# PX4FMUv2_4_6_02.net
KiCad netlist of a schematic drawn in Altium Designer
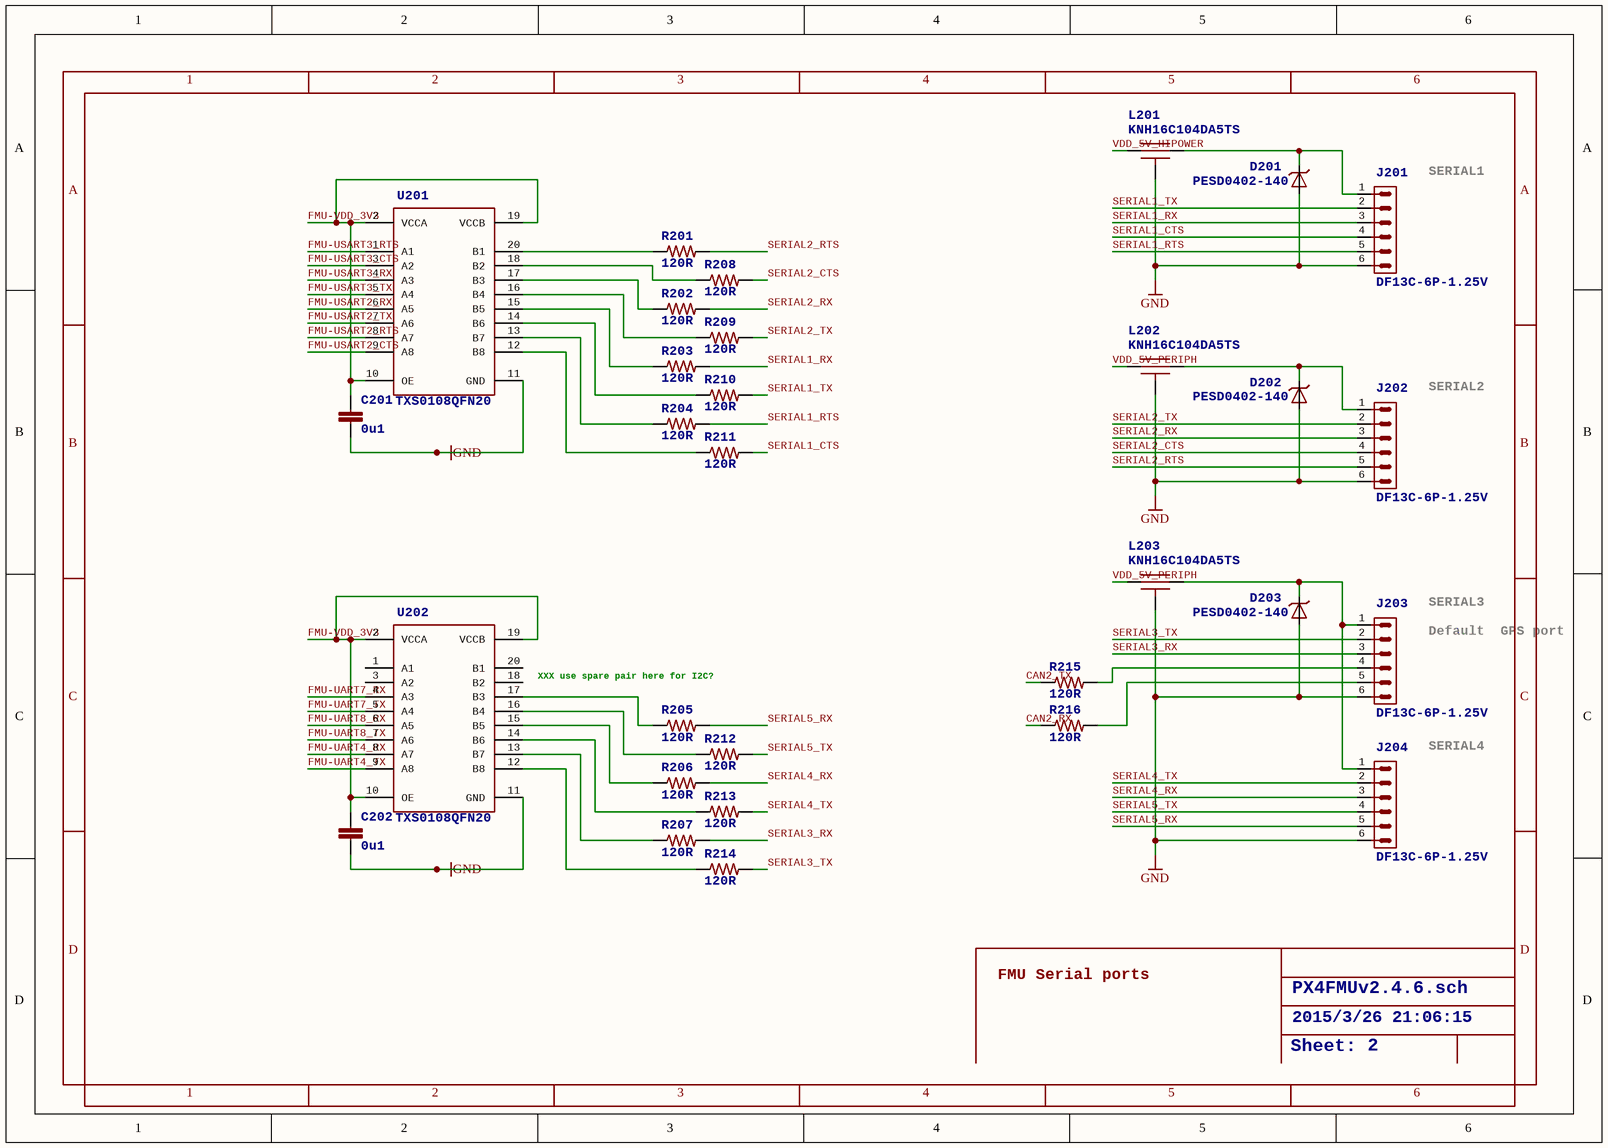
[diagram p0: PX4FMUv2.4.6_02.SchDoc]

(export (version "E")
  (design (tool "Eeschema 10.0.6"))
  (components
    (comp (ref "C201")
      (value "0u1")
      (footprint "0402-CAP")
      (description "<b>Capacitor</b>\nStandard 0603 ceramic capacitor, and 0.1\" leaded capacitor.")
      (fields (field (name "PARTNO") "CC0402ZRY5V7BB104"))
      (libsource (lib "pixhawk2") (part "CAP0402"))
    )
    (comp (ref "C202")
      (value "0u1")
      (footprint "0402-CAP")
      (description "<b>Capacitor</b>\nStandard 0603 ceramic capacitor, and 0.1\" leaded capacitor.")
      (fields (field (name "PARTNO") "CC0402ZRY5V7BB104"))
      (libsource (lib "pixhawk2") (part "CAP0402"))
    )
    (comp (ref "D201")
      (value "PESD0402-140")
      (footprint "0402-TVS")
      (libsource (lib "pixhawk2") (part "DIODE-TVS"))
    )
    (comp (ref "D202")
      (value "PESD0402-140")
      (footprint "0402-TVS")
      (libsource (lib "pixhawk2") (part "DIODE-TVS"))
    )
    (comp (ref "D203")
      (value "PESD0402-140")
      (footprint "0402-TVS")
      (libsource (lib "pixhawk2") (part "DIODE-TVS"))
    )
    (comp (ref "J201")
      (value "DF13C-6P-1.25V")
      (footprint "DF13C-6P-1.25V")
      (description "DF13-6P\n1.25mm Pitch Miniature Crimping Connector.")
      (fields (field (name "PARTNO") "DF13C-6P-1.25V(20)"))
      (libsource (lib "con-hirose-df13") (part "DF13-6P-1.25V"))
    )
    (comp (ref "J202")
      (value "DF13C-6P-1.25V")
      (footprint "DF13C-6P-1.25V")
      (description "DF13-6P\n1.25mm Pitch Miniature Crimping Connector.")
      (fields (field (name "PARTNO") "DF13C-6P-1.25V(20)"))
      (libsource (lib "con-hirose-df13") (part "DF13-6P-1.25V"))
    )
    (comp (ref "J203")
      (value "DF13C-6P-1.25V")
      (footprint "DF13C-6P-1.25V")
      (description "DF13-6P\n1.25mm Pitch Miniature Crimping Connector.")
      (fields (field (name "PARTNO") "DF13C-6P-1.25V(20)"))
      (libsource (lib "con-hirose-df13") (part "DF13-6P-1.25V"))
    )
    (comp (ref "J204")
      (value "DF13C-6P-1.25V")
      (footprint "DF13C-6P-1.25V")
      (description "DF13-6P\n1.25mm Pitch Miniature Crimping Connector.")
      (fields (field (name "PARTNO") "DF13C-6P-1.25V(20)"))
      (libsource (lib "con-hirose-df13") (part "DF13-6P-1.25V"))
    )
    (comp (ref "L201")
      (value "KNH16C104DA5TS")
      (footprint "KYOCERA-KNH16-DA")
      (description "Kyocera KNH16C104DA5TS EMI filter")
      (libsource (lib "pixhawk2") (part "KNH16C104DA5TS"))
    )
    (comp (ref "L202")
      (value "KNH16C104DA5TS")
      (footprint "KYOCERA-KNH16-DA")
      (description "Kyocera KNH16C104DA5TS EMI filter")
      (libsource (lib "pixhawk2") (part "KNH16C104DA5TS"))
    )
    (comp (ref "L203")
      (value "KNH16C104DA5TS")
      (footprint "KYOCERA-KNH16-DA")
      (description "Kyocera KNH16C104DA5TS EMI filter")
      (libsource (lib "pixhawk2") (part "KNH16C104DA5TS"))
    )
    (comp (ref "R201")
      (value "120R")
      (footprint "0402-RES")
      (fields (field (name "PARTNO") "RC0402FR-07120RL"))
      (libsource (lib "pixhawk2") (part "RESISTOR0402-RES"))
    )
    (comp (ref "R202")
      (value "120R")
      (footprint "0402-RES")
      (fields (field (name "PARTNO") "RC0402FR-07120RL"))
      (libsource (lib "pixhawk2") (part "RESISTOR0402-RES"))
    )
    (comp (ref "R203")
      (value "120R")
      (footprint "0402-RES")
      (fields (field (name "PARTNO") "RC0402FR-07120RL"))
      (libsource (lib "pixhawk2") (part "RESISTOR0402-RES"))
    )
    (comp (ref "R204")
      (value "120R")
      (footprint "0402-RES")
      (fields (field (name "PARTNO") "RC0402FR-07120RL"))
      (libsource (lib "pixhawk2") (part "RESISTOR0402-RES"))
    )
    (comp (ref "R205")
      (value "120R")
      (footprint "0402-RES")
      (fields (field (name "PARTNO") "RC0402FR-07120RL"))
      (libsource (lib "pixhawk2") (part "RESISTOR0402-RES"))
    )
    (comp (ref "R206")
      (value "120R")
      (footprint "0402-RES")
      (fields (field (name "PARTNO") "RC0402FR-07120RL"))
      (libsource (lib "pixhawk2") (part "RESISTOR0402-RES"))
    )
    (comp (ref "R207")
      (value "120R")
      (footprint "0402-RES")
      (fields (field (name "PARTNO") "RC0402FR-07120RL"))
      (libsource (lib "pixhawk2") (part "RESISTOR0402-RES"))
    )
    (comp (ref "R208")
      (value "120R")
      (footprint "0402-RES")
      (fields (field (name "PARTNO") "RC0402FR-07120RL"))
      (libsource (lib "pixhawk2") (part "RESISTOR0402-RES"))
    )
    (comp (ref "R209")
      (value "120R")
      (footprint "0402-RES")
      (fields (field (name "PARTNO") "RC0402FR-07120RL"))
      (libsource (lib "pixhawk2") (part "RESISTOR0402-RES"))
    )
    (comp (ref "R210")
      (value "120R")
      (footprint "0402-RES")
      (fields (field (name "PARTNO") "RC0402FR-07120RL"))
      (libsource (lib "pixhawk2") (part "RESISTOR0402-RES"))
    )
    (comp (ref "R211")
      (value "120R")
      (footprint "0402-RES")
      (fields (field (name "PARTNO") "RC0402FR-07120RL"))
      (libsource (lib "pixhawk2") (part "RESISTOR0402-RES"))
    )
    (comp (ref "R212")
      (value "120R")
      (footprint "0402-RES")
      (fields (field (name "PARTNO") "RC0402FR-07120RL"))
      (libsource (lib "pixhawk2") (part "RESISTOR0402-RES"))
    )
    (comp (ref "R213")
      (value "120R")
      (footprint "0402-RES")
      (fields (field (name "PARTNO") "RC0402FR-07120RL"))
      (libsource (lib "pixhawk2") (part "RESISTOR0402-RES"))
    )
    (comp (ref "R214")
      (value "120R")
      (footprint "0402-RES")
      (fields (field (name "PARTNO") "RC0402FR-07120RL"))
      (libsource (lib "pixhawk2") (part "RESISTOR0402-RES"))
    )
    (comp (ref "R215")
      (value "120R")
      (footprint "0402-RES")
      (fields (field (name "PARTNO") "RC0402FR-07120RL"))
      (libsource (lib "pixhawk2") (part "RESISTOR0402-RES"))
    )
    (comp (ref "R216")
      (value "120R")
      (footprint "0402-RES")
      (fields (field (name "PARTNO") "RC0402FR-07120RL"))
      (libsource (lib "pixhawk2") (part "RESISTOR0402-RES"))
    )
    (comp (ref "U201")
      (value "TXS0108QFN20")
      (footprint "QFN20-RGY")
      (fields (field (name "PARTNO") "TXS0108ERGYR"))
      (libsource (lib "pixhawk2") (part "TXS0108QFN20"))
    )
    (comp (ref "U202")
      (value "TXS0108QFN20")
      (footprint "QFN20-RGY")
      (fields (field (name "PARTNO") "TXS0108ERGYR"))
      (libsource (lib "pixhawk2") (part "TXS0108QFN20"))
    )
  )
  (nets
    (net (code "1") (name "/CAN2_RX") (class "Default")
      (node (ref "R216") (pin "P$1") (pinfunction "1_P$1") (pintype "passive"))
    )
    (net (code "2") (name "/CAN2_TX") (class "Default")
      (node (ref "R215") (pin "P$1") (pinfunction "1_P$1") (pintype "passive"))
    )
    (net (code "3") (name "/FMU-UART4_RX") (class "Default")
      (node (ref "U202") (pin "8") (pinfunction "A7_8") (pintype "passive"))
    )
    (net (code "4") (name "/FMU-UART4_TX") (class "Default")
      (node (ref "U202") (pin "9") (pinfunction "A8_9") (pintype "passive"))
    )
    (net (code "5") (name "/FMU-UART7_RX") (class "Default")
      (node (ref "U202") (pin "4") (pinfunction "A3_4") (pintype "passive"))
    )
    (net (code "6") (name "/FMU-UART7_TX") (class "Default")
      (node (ref "U202") (pin "5") (pinfunction "A4_5") (pintype "passive"))
    )
    (net (code "7") (name "/FMU-UART8_RX") (class "Default")
      (node (ref "U202") (pin "6") (pinfunction "A5_6") (pintype "passive"))
    )
    (net (code "8") (name "/FMU-UART8_TX") (class "Default")
      (node (ref "U202") (pin "7") (pinfunction "A6_7") (pintype "passive"))
    )
    (net (code "9") (name "/FMU-USART2_CTS") (class "Default")
      (node (ref "U201") (pin "9") (pinfunction "A8_9") (pintype "passive"))
    )
    (net (code "10") (name "/FMU-USART2_RTS") (class "Default")
      (node (ref "U201") (pin "8") (pinfunction "A7_8") (pintype "passive"))
    )
    (net (code "11") (name "/FMU-USART2_RX") (class "Default")
      (node (ref "U201") (pin "6") (pinfunction "A5_6") (pintype "passive"))
    )
    (net (code "12") (name "/FMU-USART2_TX") (class "Default")
      (node (ref "U201") (pin "7") (pinfunction "A6_7") (pintype "passive"))
    )
    (net (code "13") (name "/FMU-USART3_CTS") (class "Default")
      (node (ref "U201") (pin "3") (pinfunction "A2_3") (pintype "passive"))
    )
    (net (code "14") (name "/FMU-USART3_RTS") (class "Default")
      (node (ref "U201") (pin "1") (pinfunction "A1_1") (pintype "passive"))
    )
    (net (code "15") (name "/FMU-USART3_RX") (class "Default")
      (node (ref "U201") (pin "4") (pinfunction "A3_4") (pintype "passive"))
    )
    (net (code "16") (name "/FMU-USART3_TX") (class "Default")
      (node (ref "U201") (pin "5") (pinfunction "A4_5") (pintype "passive"))
    )
    (net (code "17") (name "/FMU-VDD_3V3") (class "Default")
      (node (ref "C201") (pin "P$1") (pinfunction "1_P$1") (pintype "passive"))
      (node (ref "C202") (pin "P$1") (pinfunction "1_P$1") (pintype "passive"))
      (node (ref "U201") (pin "10") (pinfunction "OE_10") (pintype "passive"))
      (node (ref "U201") (pin "19") (pinfunction "VCCB_19") (pintype "passive"))
      (node (ref "U201") (pin "2") (pinfunction "VCCA_2") (pintype "passive"))
      (node (ref "U202") (pin "10") (pinfunction "OE_10") (pintype "passive"))
      (node (ref "U202") (pin "19") (pinfunction "VCCB_19") (pintype "passive"))
      (node (ref "U202") (pin "2") (pinfunction "VCCA_2") (pintype "passive"))
    )
    (net (code "18") (name "/SERIAL1_CTS") (class "Default")
      (node (ref "J201") (pin "4") (pinfunction "4_4") (pintype "passive"))
      (node (ref "R211") (pin "P$2") (pinfunction "2_P$2") (pintype "passive"))
    )
    (net (code "19") (name "/SERIAL1_RTS") (class "Default")
      (node (ref "J201") (pin "5") (pinfunction "5_5") (pintype "passive"))
      (node (ref "R204") (pin "P$2") (pinfunction "2_P$2") (pintype "passive"))
    )
    (net (code "20") (name "/SERIAL1_RX") (class "Default")
      (node (ref "J201") (pin "3") (pinfunction "3_3") (pintype "passive"))
      (node (ref "R203") (pin "P$2") (pinfunction "2_P$2") (pintype "passive"))
    )
    (net (code "21") (name "/SERIAL1_TX") (class "Default")
      (node (ref "J201") (pin "2") (pinfunction "2_2") (pintype "passive"))
      (node (ref "R210") (pin "P$2") (pinfunction "2_P$2") (pintype "passive"))
    )
    (net (code "22") (name "/SERIAL2_CTS") (class "Default")
      (node (ref "J202") (pin "4") (pinfunction "4_4") (pintype "passive"))
      (node (ref "R208") (pin "P$2") (pinfunction "2_P$2") (pintype "passive"))
    )
    (net (code "23") (name "/SERIAL2_RTS") (class "Default")
      (node (ref "J202") (pin "5") (pinfunction "5_5") (pintype "passive"))
      (node (ref "R201") (pin "P$2") (pinfunction "2_P$2") (pintype "passive"))
    )
    (net (code "24") (name "/SERIAL2_RX") (class "Default")
      (node (ref "J202") (pin "3") (pinfunction "3_3") (pintype "passive"))
      (node (ref "R202") (pin "P$2") (pinfunction "2_P$2") (pintype "passive"))
    )
    (net (code "25") (name "/SERIAL2_TX") (class "Default")
      (node (ref "J202") (pin "2") (pinfunction "2_2") (pintype "passive"))
      (node (ref "R209") (pin "P$2") (pinfunction "2_P$2") (pintype "passive"))
    )
    (net (code "26") (name "/SERIAL3_RX") (class "Default")
      (node (ref "J203") (pin "3") (pinfunction "3_3") (pintype "passive"))
      (node (ref "R207") (pin "P$2") (pinfunction "2_P$2") (pintype "passive"))
    )
    (net (code "27") (name "/SERIAL3_TX") (class "Default")
      (node (ref "J203") (pin "2") (pinfunction "2_2") (pintype "passive"))
      (node (ref "R214") (pin "P$2") (pinfunction "2_P$2") (pintype "passive"))
    )
    (net (code "28") (name "/SERIAL4_RX") (class "Default")
      (node (ref "J204") (pin "3") (pinfunction "3_3") (pintype "passive"))
      (node (ref "R206") (pin "P$2") (pinfunction "2_P$2") (pintype "passive"))
    )
    (net (code "29") (name "/SERIAL4_TX") (class "Default")
      (node (ref "J204") (pin "2") (pinfunction "2_2") (pintype "passive"))
      (node (ref "R213") (pin "P$2") (pinfunction "2_P$2") (pintype "passive"))
    )
    (net (code "30") (name "/SERIAL5_RX") (class "Default")
      (node (ref "J204") (pin "5") (pinfunction "5_5") (pintype "passive"))
      (node (ref "R205") (pin "P$2") (pinfunction "2_P$2") (pintype "passive"))
    )
    (net (code "31") (name "/SERIAL5_TX") (class "Default")
      (node (ref "J204") (pin "4") (pinfunction "4_4") (pintype "passive"))
      (node (ref "R212") (pin "P$2") (pinfunction "2_P$2") (pintype "passive"))
    )
    (net (code "32") (name "/VDD_5V_HIPOWER") (class "Default")
      (node (ref "L201") (pin "P$1") (pinfunction "P$1_P$1") (pintype "passive"))
    )
    (net (code "33") (name "/VDD_5V_PERIPH") (class "Default")
      (node (ref "L202") (pin "P$1") (pinfunction "P$1_P$1") (pintype "passive"))
      (node (ref "L203") (pin "P$1") (pinfunction "P$1_P$1") (pintype "passive"))
    )
    (net (code "34") (name "GND") (class "Default")
      (node (ref "C201") (pin "P$2") (pinfunction "2_P$2") (pintype "passive"))
      (node (ref "C202") (pin "P$2") (pinfunction "2_P$2") (pintype "passive"))
      (node (ref "D201") (pin "A") (pinfunction "A_A") (pintype "passive"))
      (node (ref "D202") (pin "A") (pinfunction "A_A") (pintype "passive"))
      (node (ref "D203") (pin "A") (pinfunction "A_A") (pintype "passive"))
      (node (ref "J201") (pin "6") (pinfunction "6_6") (pintype "passive"))
      (node (ref "J202") (pin "6") (pinfunction "6_6") (pintype "passive"))
      (node (ref "J203") (pin "6") (pinfunction "6_6") (pintype "passive"))
      (node (ref "J204") (pin "6") (pinfunction "6_6") (pintype "passive"))
      (node (ref "L201") (pin "P$3_P$4_P$5") (pinfunction "P$3_P$3_P$4_P$5") (pintype "passive"))
      (node (ref "L202") (pin "P$3_P$4_P$5") (pinfunction "P$3_P$3_P$4_P$5") (pintype "passive"))
      (node (ref "L203") (pin "P$3_P$4_P$5") (pinfunction "P$3_P$3_P$4_P$5") (pintype "passive"))
      (node (ref "U201") (pin "11") (pinfunction "GND_11") (pintype "open_emitter"))
      (node (ref "U202") (pin "11") (pinfunction "GND_11") (pintype "open_emitter"))
    )
    (net (code "35") (name "Net-(D201-PadC)") (class "Default")
      (node (ref "D201") (pin "C") (pinfunction "C_C") (pintype "passive"))
      (node (ref "J201") (pin "1") (pinfunction "1_1") (pintype "passive"))
      (node (ref "L201") (pin "P$2") (pinfunction "P$2_P$2") (pintype "passive"))
    )
    (net (code "36") (name "Net-(D202-PadC)") (class "Default")
      (node (ref "D202") (pin "C") (pinfunction "C_C") (pintype "passive"))
      (node (ref "J202") (pin "1") (pinfunction "1_1") (pintype "passive"))
      (node (ref "L202") (pin "P$2") (pinfunction "P$2_P$2") (pintype "passive"))
    )
    (net (code "37") (name "Net-(D203-PadC)") (class "Default")
      (node (ref "D203") (pin "C") (pinfunction "C_C") (pintype "passive"))
      (node (ref "J203") (pin "1") (pinfunction "1_1") (pintype "passive"))
      (node (ref "J204") (pin "1") (pinfunction "1_1") (pintype "passive"))
      (node (ref "L203") (pin "P$2") (pinfunction "P$2_P$2") (pintype "passive"))
    )
    (net (code "38") (name "Net-(R201-1)") (class "Default")
      (node (ref "R201") (pin "P$1") (pinfunction "1_P$1") (pintype "passive"))
      (node (ref "U201") (pin "20") (pinfunction "B1_20") (pintype "passive"))
    )
    (net (code "39") (name "Net-(R202-1)") (class "Default")
      (node (ref "R202") (pin "P$1") (pinfunction "1_P$1") (pintype "passive"))
      (node (ref "U201") (pin "17") (pinfunction "B3_17") (pintype "passive"))
    )
    (net (code "40") (name "Net-(R203-1)") (class "Default")
      (node (ref "R203") (pin "P$1") (pinfunction "1_P$1") (pintype "passive"))
      (node (ref "U201") (pin "15") (pinfunction "B5_15") (pintype "passive"))
    )
    (net (code "41") (name "Net-(R204-1)") (class "Default")
      (node (ref "R204") (pin "P$1") (pinfunction "1_P$1") (pintype "passive"))
      (node (ref "U201") (pin "13") (pinfunction "B7_13") (pintype "passive"))
    )
    (net (code "42") (name "Net-(R205-1)") (class "Default")
      (node (ref "R205") (pin "P$1") (pinfunction "1_P$1") (pintype "passive"))
      (node (ref "U202") (pin "17") (pinfunction "B3_17") (pintype "passive"))
    )
    (net (code "43") (name "Net-(R206-1)") (class "Default")
      (node (ref "R206") (pin "P$1") (pinfunction "1_P$1") (pintype "passive"))
      (node (ref "U202") (pin "15") (pinfunction "B5_15") (pintype "passive"))
    )
    (net (code "44") (name "Net-(R207-1)") (class "Default")
      (node (ref "R207") (pin "P$1") (pinfunction "1_P$1") (pintype "passive"))
      (node (ref "U202") (pin "13") (pinfunction "B7_13") (pintype "passive"))
    )
    (net (code "45") (name "Net-(R208-1)") (class "Default")
      (node (ref "R208") (pin "P$1") (pinfunction "1_P$1") (pintype "passive"))
      (node (ref "U201") (pin "18") (pinfunction "B2_18") (pintype "passive"))
    )
    (net (code "46") (name "Net-(R209-1)") (class "Default")
      (node (ref "R209") (pin "P$1") (pinfunction "1_P$1") (pintype "passive"))
      (node (ref "U201") (pin "16") (pinfunction "B4_16") (pintype "passive"))
    )
    (net (code "47") (name "Net-(R210-1)") (class "Default")
      (node (ref "R210") (pin "P$1") (pinfunction "1_P$1") (pintype "passive"))
      (node (ref "U201") (pin "14") (pinfunction "B6_14") (pintype "passive"))
    )
    (net (code "48") (name "Net-(R211-1)") (class "Default")
      (node (ref "R211") (pin "P$1") (pinfunction "1_P$1") (pintype "passive"))
      (node (ref "U201") (pin "12") (pinfunction "B8_12") (pintype "passive"))
    )
    (net (code "49") (name "Net-(R212-1)") (class "Default")
      (node (ref "R212") (pin "P$1") (pinfunction "1_P$1") (pintype "passive"))
      (node (ref "U202") (pin "16") (pinfunction "B4_16") (pintype "passive"))
    )
    (net (code "50") (name "Net-(R213-1)") (class "Default")
      (node (ref "R213") (pin "P$1") (pinfunction "1_P$1") (pintype "passive"))
      (node (ref "U202") (pin "14") (pinfunction "B6_14") (pintype "passive"))
    )
    (net (code "51") (name "Net-(R214-1)") (class "Default")
      (node (ref "R214") (pin "P$1") (pinfunction "1_P$1") (pintype "passive"))
      (node (ref "U202") (pin "12") (pinfunction "B8_12") (pintype "passive"))
    )
    (net (code "52") (name "Net-(R215-2)") (class "Default")
      (node (ref "J203") (pin "4") (pinfunction "4_4") (pintype "passive"))
      (node (ref "R215") (pin "P$2") (pinfunction "2_P$2") (pintype "passive"))
    )
    (net (code "53") (name "Net-(R216-2)") (class "Default")
      (node (ref "J203") (pin "5") (pinfunction "5_5") (pintype "passive"))
      (node (ref "R216") (pin "P$2") (pinfunction "2_P$2") (pintype "passive"))
    )
    (net (code "54") (name "unconnected-(U202-A1-Pad1)") (class "Default")
      (node (ref "U202") (pin "1") (pinfunction "A1_1") (pintype "passive"))
    )
    (net (code "55") (name "unconnected-(U202-A2-Pad3)") (class "Default")
      (node (ref "U202") (pin "3") (pinfunction "A2_3") (pintype "passive"))
    )
    (net (code "56") (name "unconnected-(U202-B1-Pad20)") (class "Default")
      (node (ref "U202") (pin "20") (pinfunction "B1_20") (pintype "passive"))
    )
    (net (code "57") (name "unconnected-(U202-B2-Pad18)") (class "Default")
      (node (ref "U202") (pin "18") (pinfunction "B2_18") (pintype "passive"))
    )
  )
)
